# Schematic.net
KiCad netlist of a schematic drawn in EAGLE
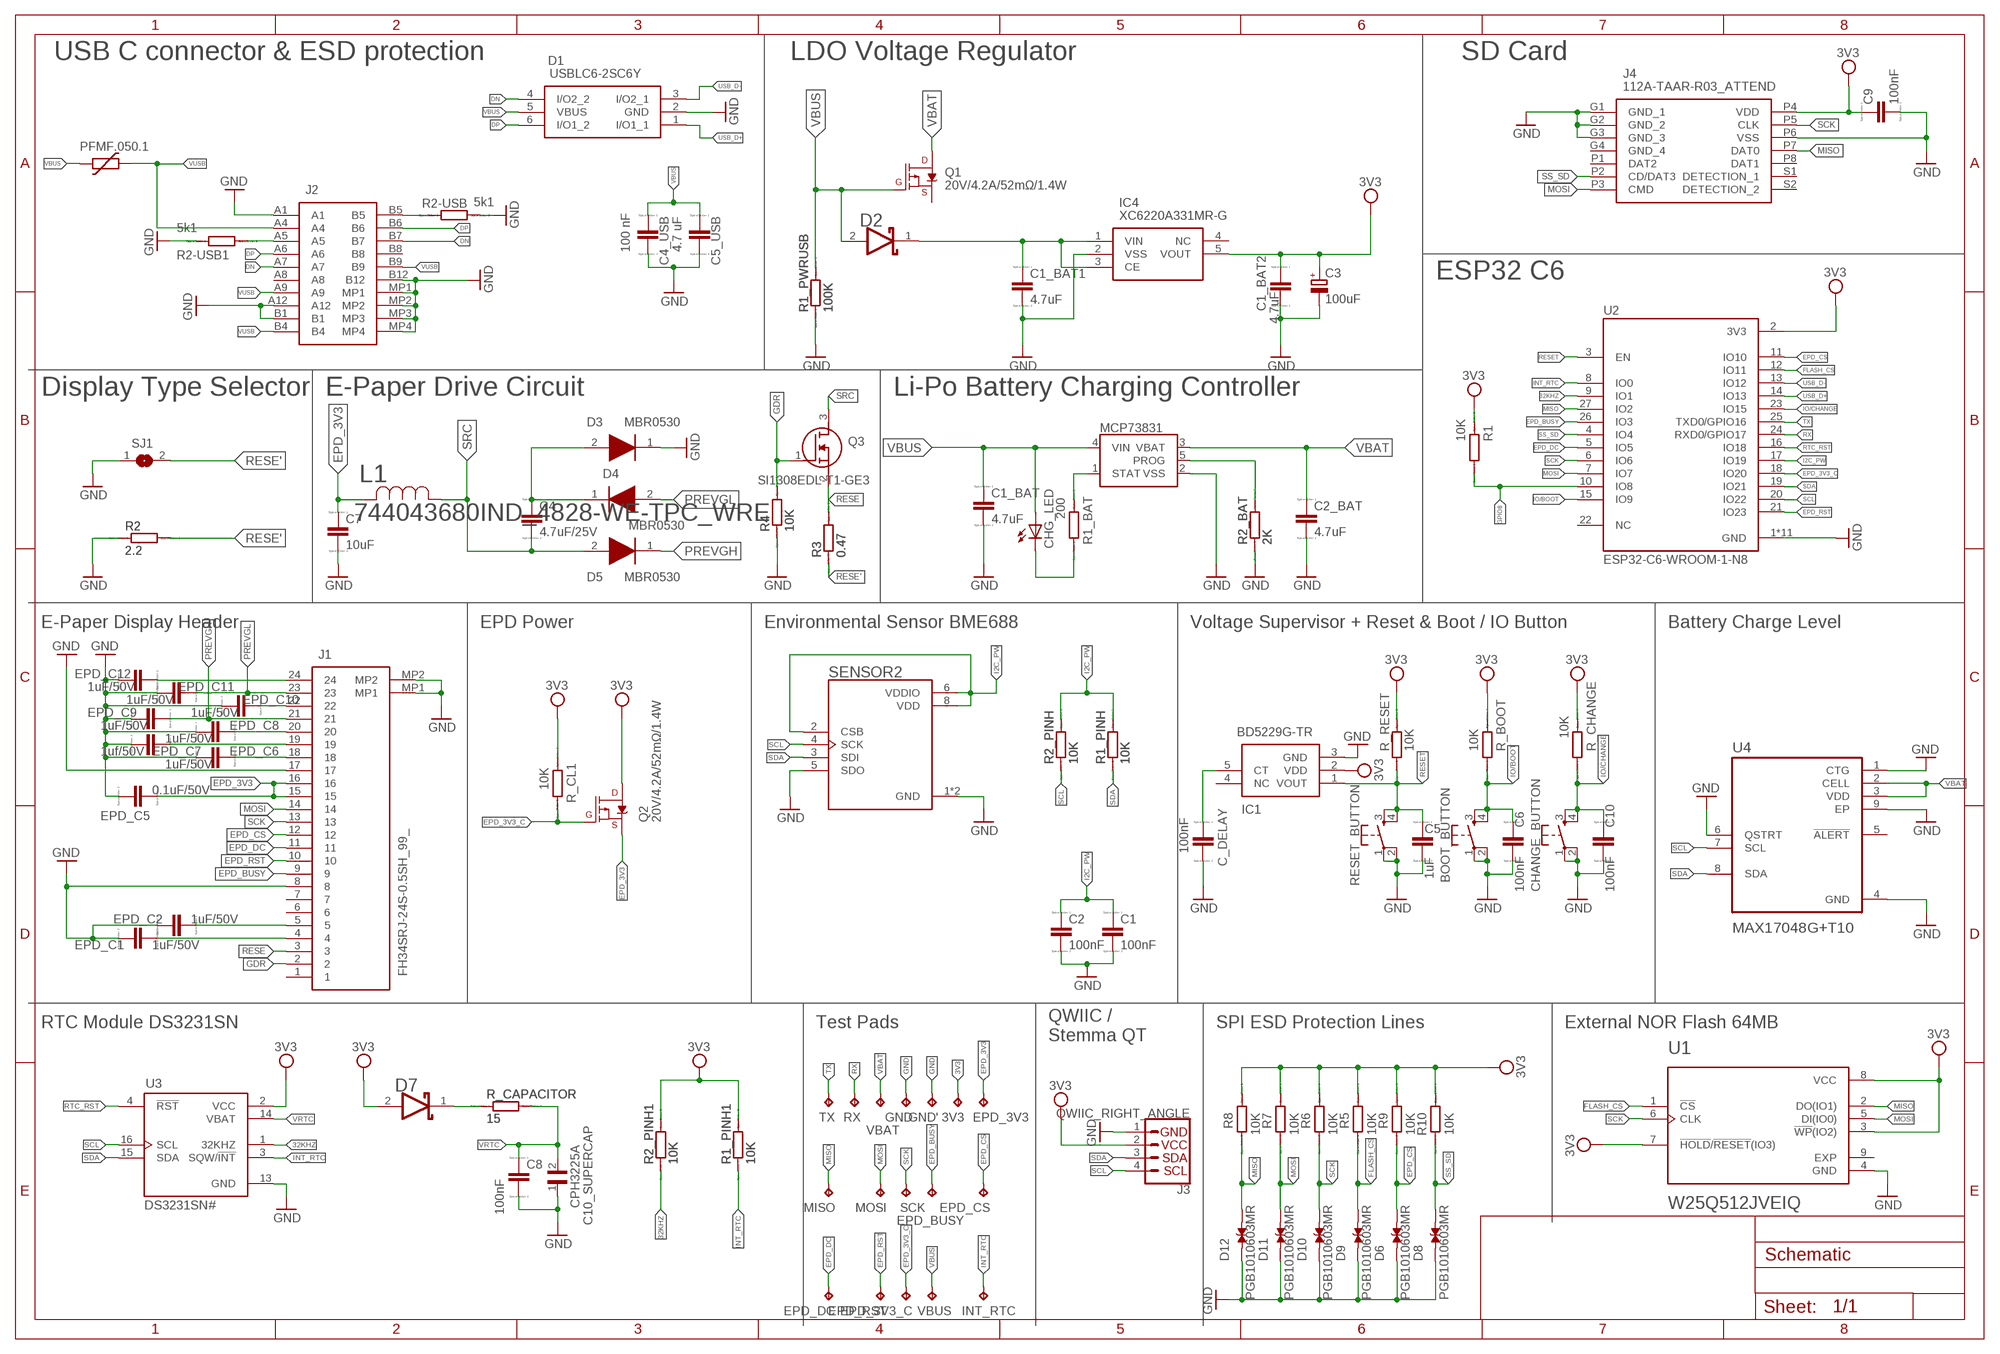
[diagram p0: schematic, sheet 1]

(export (version "E")
  (design (tool "Eeschema 10.0.6"))
  (components
    (comp (ref "3V3")
      (value "TPTP20R")
      (footprint "eagle-import:TP20R")
      (libsource (lib "eagle-import") (part "TPTP20R"))
    )
    (comp (ref "BOOT_BUTTON")
      (value "BUTTON_CUSYOMV1PACKAGE")
      (footprint "eagle-import:MYBUTTON")
      (libsource (lib "eagle-import") (part "BUTTON_CUSYOMV1PACKAGE"))
    )
    (comp (ref "C1")
      (value "100nF")
      (footprint "eagle-import:EAGLE-LTSPICE_C0402")
      (libsource (lib "eagle-import") (part "EAGLE-LTSPICE_CC0402"))
    )
    (comp (ref "C1_BAT")
      (value "4.7uF")
      (footprint "eagle-import:EAGLE-LTSPICE_C0402")
      (libsource (lib "eagle-import") (part "EAGLE-LTSPICE_CC0402"))
    )
    (comp (ref "C1_BAT1")
      (value "4.7uF")
      (footprint "eagle-import:EAGLE-LTSPICE_C0402")
      (libsource (lib "eagle-import") (part "EAGLE-LTSPICE_CC0402"))
    )
    (comp (ref "C1_BAT2")
      (value "4.7uF")
      (footprint "eagle-import:EAGLE-LTSPICE_C0402")
      (libsource (lib "eagle-import") (part "EAGLE-LTSPICE_CC0402"))
    )
    (comp (ref "C2")
      (value "100nF")
      (footprint "eagle-import:EAGLE-LTSPICE_C0402")
      (libsource (lib "eagle-import") (part "EAGLE-LTSPICE_CC0402"))
    )
    (comp (ref "C2_BAT")
      (value "4.7uF")
      (footprint "eagle-import:EAGLE-LTSPICE_C0402")
      (libsource (lib "eagle-import") (part "EAGLE-LTSPICE_CC0402"))
    )
    (comp (ref "C3")
      (value "100uF")
      (footprint "eagle-import:RCL_CT3528")
      (libsource (lib "eagle-import") (part "RCL_CPOL-EUCT3528"))
    )
    (comp (ref "C4")
      (value "4.7uF/25V")
      (footprint "eagle-import:EAGLE-LTSPICE_C0402")
      (libsource (lib "eagle-import") (part "EAGLE-LTSPICE_CC0402"))
    )
    (comp (ref "C4_USB")
      (value "100 nF")
      (footprint "eagle-import:EAGLE-LTSPICE_C0402")
      (libsource (lib "eagle-import") (part "EAGLE-LTSPICE_CC0402"))
    )
    (comp (ref "C5")
      (value "1uF")
      (footprint "eagle-import:EAGLE-LTSPICE_C0402")
      (libsource (lib "eagle-import") (part "EAGLE-LTSPICE_CC0402"))
    )
    (comp (ref "C5_USB")
      (value "4.7 uF")
      (footprint "eagle-import:EAGLE-LTSPICE_C0402")
      (libsource (lib "eagle-import") (part "EAGLE-LTSPICE_CC0402"))
    )
    (comp (ref "C6")
      (value "100nF")
      (footprint "eagle-import:EAGLE-LTSPICE_C0402")
      (libsource (lib "eagle-import") (part "EAGLE-LTSPICE_CC0402"))
    )
    (comp (ref "C7")
      (value "10uF")
      (footprint "eagle-import:EAGLE-LTSPICE_C0402")
      (libsource (lib "eagle-import") (part "EAGLE-LTSPICE_CC0402"))
    )
    (comp (ref "C8")
      (value "100nF")
      (footprint "eagle-import:EAGLE-LTSPICE_C0402")
      (libsource (lib "eagle-import") (part "EAGLE-LTSPICE_CC0402"))
    )
    (comp (ref "C9")
      (value "100nF")
      (footprint "eagle-import:EAGLE-LTSPICE_C0402")
      (libsource (lib "eagle-import") (part "EAGLE-LTSPICE_CC0402"))
    )
    (comp (ref "C10")
      (value "100nF")
      (footprint "eagle-import:EAGLE-LTSPICE_C0402")
      (libsource (lib "eagle-import") (part "EAGLE-LTSPICE_CC0402"))
    )
    (comp (ref "C10_SUPERCAP")
      (value "CPH3225A")
      (footprint "eagle-import:CAPCP3225X100N")
      (fields (field (name "MF") "Seiko Instruments"))
      (libsource (lib "eagle-import") (part "CPH3225A"))
    )
    (comp (ref "CHANGE_BUTTON")
      (value "BUTTON_CUSYOMV1PACKAGE")
      (footprint "eagle-import:MYBUTTON")
      (libsource (lib "eagle-import") (part "BUTTON_CUSYOMV1PACKAGE"))
    )
    (comp (ref "CHG_LED")
      (value "ADAFRUIT_LEDCHIP-LED0603")
      (footprint "eagle-import:ADAFRUIT_CHIP-LED0603")
      (libsource (lib "eagle-import") (part "ADAFRUIT_LEDCHIP-LED0603"))
    )
    (comp (ref "C_DELAY")
      (value "100nF")
      (footprint "eagle-import:EAGLE-LTSPICE_C0402")
      (libsource (lib "eagle-import") (part "EAGLE-LTSPICE_CC0402"))
    )
    (comp (ref "D1")
      (value "USBLC6-2SC6Y")
      (footprint "eagle-import:SOT95P280X145-6N")
      (fields (field (name "MF") "STMicroelectronics"))
      (libsource (lib "eagle-import") (part "USBLC6-2SC6Y"))
    )
    (comp (ref "D2")
      (value "ESP32_WROVER_AVX---SD0805S020S1R0_AVX_SD0805S020S1R0_0_0AVX_SD0805S020S1R0_0_0")
      (footprint "eagle-import:ESP32_WROVER_AVX---SD0805S020S1R0_AVX_SD0805S020S1R0_0")
      (fields
        (field (name "DIGIKEY_PART_NUMBER") "478-7800-1-ND")
        (field (name "MF") "AVX")
        (field (name "MOUSER_PART_NUMBER") "581-SD0805S020S1R0")
      )
      (libsource (lib "eagle-import") (part "ESP32_WROVER_AVX---SD0805S020S1R0_AVX_SD0805S020S1R0_0_0AVX_SD0805S020S1R0_0_0"))
    )
    (comp (ref "D3")
      (value "MBR0530")
      (footprint "eagle-import:SOD3716X135N")
      (fields (field (name "MF") "ON Semiconductor"))
      (libsource (lib "eagle-import") (part "MBR0530"))
    )
    (comp (ref "D4")
      (value "MBR0530")
      (footprint "eagle-import:SOD3716X135N")
      (fields (field (name "MF") "ON Semiconductor"))
      (libsource (lib "eagle-import") (part "MBR0530"))
    )
    (comp (ref "D5")
      (value "MBR0530")
      (footprint "eagle-import:SOD3716X135N")
      (fields (field (name "MF") "ON Semiconductor"))
      (libsource (lib "eagle-import") (part "MBR0530"))
    )
    (comp (ref "D6")
      (value "PGB1010603MR")
      (footprint "eagle-import:DIOC1608X36N")
      (fields (field (name "MF") "Littelfuse Inc."))
      (libsource (lib "eagle-import") (part "PGB1010603MR"))
    )
    (comp (ref "D7")
      (value "ESP32_WROVER_AVX---SD0805S020S1R0_AVX_SD0805S020S1R0_0_0AVX_SD0805S020S1R0_0_0")
      (footprint "eagle-import:ESP32_WROVER_AVX---SD0805S020S1R0_AVX_SD0805S020S1R0_0")
      (fields
        (field (name "DIGIKEY_PART_NUMBER") "478-7800-1-ND")
        (field (name "MF") "AVX")
        (field (name "MOUSER_PART_NUMBER") "581-SD0805S020S1R0")
      )
      (libsource (lib "eagle-import") (part "ESP32_WROVER_AVX---SD0805S020S1R0_AVX_SD0805S020S1R0_0_0AVX_SD0805S020S1R0_0_0"))
    )
    (comp (ref "D8")
      (value "PGB1010603MR")
      (footprint "eagle-import:DIOC1608X36N")
      (fields (field (name "MF") "Littelfuse Inc."))
      (libsource (lib "eagle-import") (part "PGB1010603MR"))
    )
    (comp (ref "D9")
      (value "PGB1010603MR")
      (footprint "eagle-import:DIOC1608X36N")
      (fields (field (name "MF") "Littelfuse Inc."))
      (libsource (lib "eagle-import") (part "PGB1010603MR"))
    )
    (comp (ref "D10")
      (value "PGB1010603MR")
      (footprint "eagle-import:DIOC1608X36N")
      (fields (field (name "MF") "Littelfuse Inc."))
      (libsource (lib "eagle-import") (part "PGB1010603MR"))
    )
    (comp (ref "D11")
      (value "PGB1010603MR")
      (footprint "eagle-import:DIOC1608X36N")
      (fields (field (name "MF") "Littelfuse Inc."))
      (libsource (lib "eagle-import") (part "PGB1010603MR"))
    )
    (comp (ref "D12")
      (value "PGB1010603MR")
      (footprint "eagle-import:DIOC1608X36N")
      (fields (field (name "MF") "Littelfuse Inc."))
      (libsource (lib "eagle-import") (part "PGB1010603MR"))
    )
    (comp (ref "EPD_3V3")
      (value "TPTP20R")
      (footprint "eagle-import:TP20R")
      (libsource (lib "eagle-import") (part "TPTP20R"))
    )
    (comp (ref "EPD_3V3_C")
      (value "TPTP20R")
      (footprint "eagle-import:TP20R")
      (libsource (lib "eagle-import") (part "TPTP20R"))
    )
    (comp (ref "EPD_BUSY")
      (value "TPTP20R")
      (footprint "eagle-import:TP20R")
      (libsource (lib "eagle-import") (part "TPTP20R"))
    )
    (comp (ref "EPD_C1")
      (value "1uF/50V")
      (footprint "eagle-import:EAGLE-LTSPICE_C0402")
      (libsource (lib "eagle-import") (part "EAGLE-LTSPICE_CC0402"))
    )
    (comp (ref "EPD_C2")
      (value "1uF/50V")
      (footprint "eagle-import:EAGLE-LTSPICE_C0402")
      (libsource (lib "eagle-import") (part "EAGLE-LTSPICE_CC0402"))
    )
    (comp (ref "EPD_C5")
      (value "0.1uF/50V")
      (footprint "eagle-import:EAGLE-LTSPICE_C0402")
      (libsource (lib "eagle-import") (part "EAGLE-LTSPICE_CC0402"))
    )
    (comp (ref "EPD_C6")
      (value "1uF/50V")
      (footprint "eagle-import:EAGLE-LTSPICE_C0402")
      (libsource (lib "eagle-import") (part "EAGLE-LTSPICE_CC0402"))
    )
    (comp (ref "EPD_C7")
      (value "1uf/50V")
      (footprint "eagle-import:EAGLE-LTSPICE_C0402")
      (libsource (lib "eagle-import") (part "EAGLE-LTSPICE_CC0402"))
    )
    (comp (ref "EPD_C8")
      (value "1uF/50V")
      (footprint "eagle-import:EAGLE-LTSPICE_C0402")
      (libsource (lib "eagle-import") (part "EAGLE-LTSPICE_CC0402"))
    )
    (comp (ref "EPD_C9")
      (value "1uF/50V")
      (footprint "eagle-import:EAGLE-LTSPICE_C0402")
      (libsource (lib "eagle-import") (part "EAGLE-LTSPICE_CC0402"))
    )
    (comp (ref "EPD_C10")
      (value "1uF/50V")
      (footprint "eagle-import:EAGLE-LTSPICE_C0402")
      (libsource (lib "eagle-import") (part "EAGLE-LTSPICE_CC0402"))
    )
    (comp (ref "EPD_C11")
      (value "1uF/50V")
      (footprint "eagle-import:EAGLE-LTSPICE_C0402")
      (libsource (lib "eagle-import") (part "EAGLE-LTSPICE_CC0402"))
    )
    (comp (ref "EPD_C12")
      (value "1uF/50V")
      (footprint "eagle-import:EAGLE-LTSPICE_C0402")
      (libsource (lib "eagle-import") (part "EAGLE-LTSPICE_CC0402"))
    )
    (comp (ref "EPD_CS")
      (value "TPTP20R")
      (footprint "eagle-import:TP20R")
      (libsource (lib "eagle-import") (part "TPTP20R"))
    )
    (comp (ref "EPD_DC")
      (value "TPTP20R")
      (footprint "eagle-import:TP20R")
      (libsource (lib "eagle-import") (part "TPTP20R"))
    )
    (comp (ref "EPD_RST")
      (value "TPTP20R")
      (footprint "eagle-import:TP20R")
      (libsource (lib "eagle-import") (part "TPTP20R"))
    )
    (comp (ref "GND")
      (value "TPTP20R")
      (footprint "eagle-import:TP20R")
      (libsource (lib "eagle-import") (part "TPTP20R"))
    )
    (comp (ref "GND'")
      (value "TPTP20R")
      (footprint "eagle-import:TP20R")
      (libsource (lib "eagle-import") (part "TPTP20R"))
    )
    (comp (ref "IC1")
      (value "BD5229G-TR")
      (footprint "eagle-import:SOT95P280X125-5N")
      (fields (field (name "MOUSER_PART_NUMBER") "755-BD5229G-TR"))
      (libsource (lib "eagle-import") (part "BD5229G-TR"))
    )
    (comp (ref "IC4")
      (value "XC6220A331MR-G")
      (footprint "eagle-import:SOT95P280X120-5N")
      (fields (field (name "MOUSER_PART_NUMBER") "865-XC6220A331MR-G"))
      (libsource (lib "eagle-import") (part "XC6220A331MR-G"))
    )
    (comp (ref "INT_RTC")
      (value "TPTP20R")
      (footprint "eagle-import:TP20R")
      (libsource (lib "eagle-import") (part "TPTP20R"))
    )
    (comp (ref "J1")
      (value "FH34SRJ-24S-0.5SH_99_")
      (footprint "eagle-import:FH34SRJ24S05SH99")
      (fields
        (field (name "MANUFACTURER_PART_NUMBER") "FH34SRJ-24S-0.5SH(99)")
        (field (name "MOUSER_PART_NUMBER") "798-FH34SRJ24S05SH99")
      )
      (libsource (lib "eagle-import") (part "FH34SRJ-24S-0.5SH_99_"))
    )
    (comp (ref "J2")
      (value "SAMACSYS_PARTS_USB4110-GF-A")
      (footprint "eagle-import:SAMACSYS_PARTS_USB4110GFA")
      (fields
        (field (name "MANUFACTURER_PART_NUMBER") "USB4110-GF-A")
        (field (name "MOUSER_PART_NUMBER") "640-USB4110-GF-A")
      )
      (libsource (lib "eagle-import") (part "SAMACSYS_PARTS_USB4110-GF-A"))
    )
    (comp (ref "J3")
      (value "QWIIC_RIGHT_ANGLE")
      (footprint "eagle-import:JST04_1MM_RA")
      (libsource (lib "eagle-import") (part "QWIIC_CONNECTORJS-1MM"))
    )
    (comp (ref "J4")
      (value "112A-TAAR-R03_ATTEND")
      (footprint "eagle-import:112ATAARR03ATTEND")
      (fields (field (name "MANUFACTURER_PART_NUMBER") "112A-TAAR-R03 ATTEND"))
      (libsource (lib "eagle-import") (part "112A-TAAR-R03_ATTEND"))
    )
    (comp (ref "L1")
      (value "744043680IND_4828-WE-TPC_WRE")
      (footprint "eagle-import:IND_4828-WE-TPC_WRE")
      (fields
        (field (name "MANUFACTURER_PART_NUMBER") "744043680")
        (field (name "COPYRIGHT") "Copyright (C) 2024 Ultra Librarian. All rights reserved.")
      )
      (libsource (lib "eagle-import") (part "744043680IND_4828-WE-TPC_WRE"))
    )
    (comp (ref "MCP73831")
      (value "ESP32_WROVER_SPARKFUN-IC-POWER_MCP73831")
      (footprint "eagle-import:ESP32_WROVER_SPARKFUN-IC-POWER_SOT23-5")
      (libsource (lib "eagle-import") (part "ESP32_WROVER_SPARKFUN-IC-POWER_MCP73831"))
    )
    (comp (ref "MISO")
      (value "TPTP20R")
      (footprint "eagle-import:TP20R")
      (libsource (lib "eagle-import") (part "TPTP20R"))
    )
    (comp (ref "MOSI")
      (value "TPTP20R")
      (footprint "eagle-import:TP20R")
      (libsource (lib "eagle-import") (part "TPTP20R"))
    )
    (comp (ref "PFMF.050.1")
      (value "VARISTOR_3216")
      (footprint "eagle-import:VARC3216X102N")
      (libsource (lib "eagle-import") (part "VARISTOR3216_"))
    )
    (comp (ref "Q1")
      (value "20V/4.2A/52mΩ/1.4W")
      (footprint "eagle-import:ESP32_WROVER_SPARKFUN-DISCRETESEMI_SOT23-3")
      (libsource (lib "eagle-import") (part "ESP32_WROVER_SPARKFUN-DISCRETESEMI_MOSFET_PCH-DMG2305UX-7"))
    )
    (comp (ref "Q2")
      (value "20V/4.2A/52mΩ/1.4W")
      (footprint "eagle-import:ESP32_WROVER_SPARKFUN-DISCRETESEMI_SOT23-3")
      (libsource (lib "eagle-import") (part "ESP32_WROVER_SPARKFUN-DISCRETESEMI_MOSFET_PCH-DMG2305UX-7"))
    )
    (comp (ref "Q3")
      (value "SI1308EDL-T1-GE3")
      (footprint "eagle-import:SOT65P210X110-3N")
      (fields (field (name "MF") "Vishay Siliconix"))
      (libsource (lib "eagle-import") (part "SI1308EDL-T1-GE3"))
    )
    (comp (ref "R1")
      (value "10K")
      (footprint "eagle-import:ESP32_WROVER_EAGLE-LTSPICE_R0402")
      (libsource (lib "eagle-import") (part "ESP32_WROVER_EAGLE-LTSPICE_RR0402"))
    )
    (comp (ref "R1_BAT")
      (value "200")
      (footprint "eagle-import:ESP32_WROVER_EAGLE-LTSPICE_R0402")
      (libsource (lib "eagle-import") (part "ESP32_WROVER_EAGLE-LTSPICE_RR0402"))
    )
    (comp (ref "R1_PINH")
      (value "10K")
      (footprint "eagle-import:ESP32_WROVER_EAGLE-LTSPICE_R0402")
      (libsource (lib "eagle-import") (part "ESP32_WROVER_EAGLE-LTSPICE_RR0402"))
    )
    (comp (ref "R1_PINH1")
      (value "10K")
      (footprint "eagle-import:ESP32_WROVER_EAGLE-LTSPICE_R0402")
      (libsource (lib "eagle-import") (part "ESP32_WROVER_EAGLE-LTSPICE_RR0402"))
    )
    (comp (ref "R1_PWRUSB")
      (value "100K")
      (footprint "eagle-import:ESP32_WROVER_EAGLE-LTSPICE_R0402")
      (libsource (lib "eagle-import") (part "ESP32_WROVER_EAGLE-LTSPICE_RR0402"))
    )
    (comp (ref "R2")
      (value "2.2")
      (footprint "eagle-import:ESP32_WROVER_EAGLE-LTSPICE_R0402")
      (libsource (lib "eagle-import") (part "ESP32_WROVER_EAGLE-LTSPICE_RR0402"))
    )
    (comp (ref "R2-USB")
      (value "5k1")
      (footprint "eagle-import:ESP32_WROVER_EAGLE-LTSPICE_R0402")
      (libsource (lib "eagle-import") (part "ESP32_WROVER_EAGLE-LTSPICE_RR0402"))
    )
    (comp (ref "R2-USB1")
      (value "5k1")
      (footprint "eagle-import:ESP32_WROVER_EAGLE-LTSPICE_R0402")
      (libsource (lib "eagle-import") (part "ESP32_WROVER_EAGLE-LTSPICE_RR0402"))
    )
    (comp (ref "R2_BAT")
      (value "2K")
      (footprint "eagle-import:ESP32_WROVER_EAGLE-LTSPICE_R0402")
      (libsource (lib "eagle-import") (part "ESP32_WROVER_EAGLE-LTSPICE_RR0402"))
    )
    (comp (ref "R2_PINH")
      (value "10K")
      (footprint "eagle-import:ESP32_WROVER_EAGLE-LTSPICE_R0402")
      (libsource (lib "eagle-import") (part "ESP32_WROVER_EAGLE-LTSPICE_RR0402"))
    )
    (comp (ref "R2_PINH1")
      (value "10K")
      (footprint "eagle-import:ESP32_WROVER_EAGLE-LTSPICE_R0402")
      (libsource (lib "eagle-import") (part "ESP32_WROVER_EAGLE-LTSPICE_RR0402"))
    )
    (comp (ref "R3")
      (value "0.47")
      (footprint "eagle-import:ESP32_WROVER_EAGLE-LTSPICE_R0402")
      (libsource (lib "eagle-import") (part "ESP32_WROVER_EAGLE-LTSPICE_RR0402"))
    )
    (comp (ref "R4")
      (value "10K")
      (footprint "eagle-import:ESP32_WROVER_EAGLE-LTSPICE_R0402")
      (libsource (lib "eagle-import") (part "ESP32_WROVER_EAGLE-LTSPICE_RR0402"))
    )
    (comp (ref "R5")
      (value "10K")
      (footprint "eagle-import:ESP32_WROVER_EAGLE-LTSPICE_R0402")
      (libsource (lib "eagle-import") (part "ESP32_WROVER_EAGLE-LTSPICE_RR0402"))
    )
    (comp (ref "R6")
      (value "10K")
      (footprint "eagle-import:ESP32_WROVER_EAGLE-LTSPICE_R0402")
      (libsource (lib "eagle-import") (part "ESP32_WROVER_EAGLE-LTSPICE_RR0402"))
    )
    (comp (ref "R7")
      (value "10K")
      (footprint "eagle-import:ESP32_WROVER_EAGLE-LTSPICE_R0402")
      (libsource (lib "eagle-import") (part "ESP32_WROVER_EAGLE-LTSPICE_RR0402"))
    )
    (comp (ref "R8")
      (value "10K")
      (footprint "eagle-import:ESP32_WROVER_EAGLE-LTSPICE_R0402")
      (libsource (lib "eagle-import") (part "ESP32_WROVER_EAGLE-LTSPICE_RR0402"))
    )
    (comp (ref "R9")
      (value "10K")
      (footprint "eagle-import:ESP32_WROVER_EAGLE-LTSPICE_R0402")
      (libsource (lib "eagle-import") (part "ESP32_WROVER_EAGLE-LTSPICE_RR0402"))
    )
    (comp (ref "R10")
      (value "10K")
      (footprint "eagle-import:ESP32_WROVER_EAGLE-LTSPICE_R0402")
      (libsource (lib "eagle-import") (part "ESP32_WROVER_EAGLE-LTSPICE_RR0402"))
    )
    (comp (ref "RESET_BUTTON")
      (value "BUTTON_CUSYOMV1PACKAGE")
      (footprint "eagle-import:MYBUTTON")
      (libsource (lib "eagle-import") (part "BUTTON_CUSYOMV1PACKAGE"))
    )
    (comp (ref "RX")
      (value "TPTP20R")
      (footprint "eagle-import:TP20R")
      (libsource (lib "eagle-import") (part "TPTP20R"))
    )
    (comp (ref "R_BOOT")
      (value "10K")
      (footprint "eagle-import:ESP32_WROVER_EAGLE-LTSPICE_R0402")
      (libsource (lib "eagle-import") (part "ESP32_WROVER_EAGLE-LTSPICE_RR0402"))
    )
    (comp (ref "R_CAPACITOR")
      (value "15")
      (footprint "eagle-import:ESP32_WROVER_EAGLE-LTSPICE_R0402")
      (libsource (lib "eagle-import") (part "ESP32_WROVER_EAGLE-LTSPICE_RR0402"))
    )
    (comp (ref "R_CHANGE")
      (value "10K")
      (footprint "eagle-import:ESP32_WROVER_EAGLE-LTSPICE_R0402")
      (libsource (lib "eagle-import") (part "ESP32_WROVER_EAGLE-LTSPICE_RR0402"))
    )
    (comp (ref "R_CL1")
      (value "10K")
      (footprint "eagle-import:ESP32_WROVER_EAGLE-LTSPICE_R0402")
      (libsource (lib "eagle-import") (part "ESP32_WROVER_EAGLE-LTSPICE_RR0402"))
    )
    (comp (ref "R_RESET")
      (value "10K")
      (footprint "eagle-import:ESP32_WROVER_EAGLE-LTSPICE_R0402")
      (libsource (lib "eagle-import") (part "ESP32_WROVER_EAGLE-LTSPICE_RR0402"))
    )
    (comp (ref "SCK")
      (value "TPTP20R")
      (footprint "eagle-import:TP20R")
      (libsource (lib "eagle-import") (part "TPTP20R"))
    )
    (comp (ref "SENSOR2")
      (value "ESP32_WROVER_BME680_BME680")
      (footprint "eagle-import:ESP32_WROVER_BME680_PSON80P300X300X100-8N")
      (fields (field (name "MF") "Bosch Sensortec") (field (name "MP") "BME680"))
      (libsource (lib "eagle-import") (part "ESP32_WROVER_BME680_BME680"))
    )
    (comp (ref "SJ1") (value "SJ") (footprint "eagle-import:SJ") (libsource (lib "eagle-import") (part "SJ")))
    (comp (ref "TX")
      (value "TPTP20R")
      (footprint "eagle-import:TP20R")
      (libsource (lib "eagle-import") (part "TPTP20R"))
    )
    (comp (ref "U1")
      (value "W25Q512JVEIQ")
      (footprint "eagle-import:SON127P600X800X80-9N")
      (fields (field (name "MF") "Winbond Electronics"))
      (libsource (lib "eagle-import") (part "W25Q512JVEIQ"))
    )
    (comp (ref "U2")
      (value "ESP32-C6-WROOM-1-N8")
      (footprint "eagle-import:XCVR_ESP32-C6-WROOM-1-N8")
      (fields (field (name "MF") "Espressif Systems"))
      (libsource (lib "eagle-import") (part "ESP32-C6-WROOM-1-N8"))
    )
    (comp (ref "U3")
      (value "DS3231SN#")
      (footprint "eagle-import:SOIC127P1032X265-16N")
      (fields (field (name "MF") "Analog Devices"))
      (libsource (lib "eagle-import") (part "DS3231SN#"))
    )
    (comp (ref "U4")
      (value "MAX17048G+T10")
      (footprint "eagle-import:SON50P200X200X80-9N")
      (fields (field (name "MF") "Analog Devices"))
      (libsource (lib "eagle-import") (part "MAX17048G+T10"))
    )
    (comp (ref "VBAT")
      (value "TPTP20R")
      (footprint "eagle-import:TP20R")
      (libsource (lib "eagle-import") (part "TPTP20R"))
    )
    (comp (ref "VBUS")
      (value "TPTP20R")
      (footprint "eagle-import:TP20R")
      (libsource (lib "eagle-import") (part "TPTP20R"))
    )
  )
  (nets
    (net (code "1") (name "3V3") (class "Default")
      (node (ref "3V3") (pin "TP") (pinfunction "TP_TP") (pintype "input"))
      (node (ref "C1_BAT2") (pin "1") (pinfunction "1_1") (pintype "passive"))
      (node (ref "C3") (pin "+") (pinfunction "+_+") (pintype "passive"))
      (node (ref "C9") (pin "1") (pinfunction "1_1") (pintype "passive"))
      (node (ref "D7") (pin "2") (pinfunction "ANODE_2") (pintype "bidirectional"))
      (node (ref "IC1") (pin "2") (pinfunction "VDD_2") (pintype "bidirectional"))
      (node (ref "IC4") (pin "5") (pinfunction "VOUT_5") (pintype "bidirectional"))
      (node (ref "J3") (pin "2") (pinfunction "2_2") (pintype "power_in"))
      (node (ref "J4") (pin "P4") (pinfunction "VDD_P4") (pintype "bidirectional"))
      (node (ref "Q2") (pin "3") (pinfunction "D_3") (pintype "bidirectional"))
      (node (ref "R1") (pin "2") (pinfunction "2_2") (pintype "passive"))
      (node (ref "R10") (pin "1") (pinfunction "1_1") (pintype "passive"))
      (node (ref "R1_PINH1") (pin "2") (pinfunction "2_2") (pintype "passive"))
      (node (ref "R2_PINH1") (pin "2") (pinfunction "2_2") (pintype "passive"))
      (node (ref "R5") (pin "1") (pinfunction "1_1") (pintype "passive"))
      (node (ref "R6") (pin "1") (pinfunction "1_1") (pintype "passive"))
      (node (ref "R7") (pin "1") (pinfunction "1_1") (pintype "passive"))
      (node (ref "R8") (pin "1") (pinfunction "1_1") (pintype "passive"))
      (node (ref "R9") (pin "1") (pinfunction "1_1") (pintype "passive"))
      (node (ref "R_BOOT") (pin "2") (pinfunction "2_2") (pintype "passive"))
      (node (ref "R_CHANGE") (pin "2") (pinfunction "2_2") (pintype "passive"))
      (node (ref "R_CL1") (pin "2") (pinfunction "2_2") (pintype "passive"))
      (node (ref "R_RESET") (pin "2") (pinfunction "2_2") (pintype "passive"))
      (node (ref "U1") (pin "3") (pinfunction "~{WP}(IO2)_3") (pintype "bidirectional"))
      (node (ref "U1") (pin "7") (pinfunction "~{HOLD}/~{RESET}(IO3)_7") (pintype "bidirectional"))
      (node (ref "U1") (pin "8") (pinfunction "VCC_8") (pintype "power_in"))
      (node (ref "U2") (pin "2") (pinfunction "3V3_2") (pintype "power_in"))
      (node (ref "U3") (pin "2") (pinfunction "VCC_2") (pintype "power_in"))
    )
    (net (code "2") (name "32KHZ") (class "Default")
      (node (ref "R2_PINH1") (pin "1") (pinfunction "1_1") (pintype "passive"))
      (node (ref "U2") (pin "9") (pinfunction "IO1_9") (pintype "bidirectional"))
      (node (ref "U3") (pin "1") (pinfunction "32KHZ_1") (pintype "output"))
    )
    (net (code "3") (name "DN") (class "Default")
      (node (ref "D1") (pin "4") (pinfunction "I/O2_2_4") (pintype "bidirectional"))
      (node (ref "J2") (pin "A7") (pinfunction "A7_A7") (pintype "bidirectional"))
      (node (ref "J2") (pin "B7") (pinfunction "B7_B7") (pintype "bidirectional"))
    )
    (net (code "4") (name "DP") (class "Default")
      (node (ref "D1") (pin "6") (pinfunction "I/O1_2_6") (pintype "bidirectional"))
      (node (ref "J2") (pin "A6") (pinfunction "A6_A6") (pintype "bidirectional"))
      (node (ref "J2") (pin "B6") (pinfunction "B6_B6") (pintype "bidirectional"))
    )
    (net (code "5") (name "EPD_3V3") (class "Default")
      (node (ref "C7") (pin "1") (pinfunction "1_1") (pintype "passive"))
      (node (ref "EPD_3V3") (pin "TP") (pinfunction "TP_TP") (pintype "input"))
      (node (ref "EPD_C5") (pin "1") (pinfunction "1_1") (pintype "passive"))
      (node (ref "J1") (pin "15") (pinfunction "15_15") (pintype "bidirectional"))
      (node (ref "J1") (pin "16") (pinfunction "16_16") (pintype "bidirectional"))
      (node (ref "L1") (pin "2") (pinfunction "2_2") (pintype "passive"))
      (node (ref "Q2") (pin "2") (pinfunction "S_2") (pintype "bidirectional"))
    )
    (net (code "6") (name "EPD_3V3_C") (class "Default")
      (node (ref "EPD_3V3_C") (pin "TP") (pinfunction "TP_TP") (pintype "input"))
      (node (ref "Q2") (pin "1") (pinfunction "G_1") (pintype "bidirectional"))
      (node (ref "R_CL1") (pin "1") (pinfunction "1_1") (pintype "passive"))
      (node (ref "U2") (pin "18") (pinfunction "IO20_18") (pintype "bidirectional"))
    )
    (net (code "7") (name "EPD_BUSY") (class "Default")
      (node (ref "EPD_BUSY") (pin "TP") (pinfunction "TP_TP") (pintype "input"))
      (node (ref "J1") (pin "9") (pinfunction "9_9") (pintype "bidirectional"))
      (node (ref "U2") (pin "26") (pinfunction "IO3_26") (pintype "bidirectional"))
    )
    (net (code "8") (name "EPD_CS") (class "Default")
      (node (ref "D6") (pin "2") (pinfunction "2_2") (pintype "passive"))
      (node (ref "EPD_CS") (pin "TP") (pinfunction "TP_TP") (pintype "input"))
      (node (ref "J1") (pin "12") (pinfunction "12_12") (pintype "bidirectional"))
      (node (ref "R9") (pin "2") (pinfunction "2_2") (pintype "passive"))
      (node (ref "U2") (pin "11") (pinfunction "IO10_11") (pintype "bidirectional"))
    )
    (net (code "9") (name "EPD_DC") (class "Default")
      (node (ref "EPD_DC") (pin "TP") (pinfunction "TP_TP") (pintype "input"))
      (node (ref "J1") (pin "11") (pinfunction "11_11") (pintype "bidirectional"))
      (node (ref "U2") (pin "5") (pinfunction "IO5_5") (pintype "bidirectional"))
    )
    (net (code "10") (name "EPD_RST") (class "Default")
      (node (ref "EPD_RST") (pin "TP") (pinfunction "TP_TP") (pintype "input"))
      (node (ref "J1") (pin "10") (pinfunction "10_10") (pintype "bidirectional"))
      (node (ref "U2") (pin "21") (pinfunction "IO23_21") (pintype "bidirectional"))
    )
    (net (code "11") (name "FLASH_CS") (class "Default")
      (node (ref "D9") (pin "2") (pinfunction "2_2") (pintype "passive"))
      (node (ref "R5") (pin "2") (pinfunction "2_2") (pintype "passive"))
      (node (ref "U1") (pin "1") (pinfunction "~{CS}_1") (pintype "input"))
      (node (ref "U2") (pin "12") (pinfunction "IO11_12") (pintype "bidirectional"))
    )
    (net (code "12") (name "GDR") (class "Default")
      (node (ref "J1") (pin "2") (pinfunction "2_2") (pintype "bidirectional"))
      (node (ref "Q3") (pin "1") (pinfunction "G_1") (pintype "bidirectional"))
      (node (ref "R4") (pin "2") (pinfunction "2_2") (pintype "passive"))
    )
    (net (code "13") (name "GND") (class "Default")
      (node (ref "BOOT_BUTTON") (pin "1") (pinfunction "1_1") (pintype "passive"))
      (node (ref "BOOT_BUTTON") (pin "2") (pinfunction "2_2") (pintype "passive"))
      (node (ref "C1") (pin "2") (pinfunction "2_2") (pintype "passive"))
      (node (ref "C10") (pin "2") (pinfunction "2_2") (pintype "passive"))
      (node (ref "C10_SUPERCAP") (pin "1") (pinfunction "1_1") (pintype "passive"))
      (node (ref "C1_BAT") (pin "2") (pinfunction "2_2") (pintype "passive"))
      (node (ref "C1_BAT1") (pin "2") (pinfunction "2_2") (pintype "passive"))
      (node (ref "C1_BAT2") (pin "2") (pinfunction "2_2") (pintype "passive"))
      (node (ref "C2") (pin "2") (pinfunction "2_2") (pintype "passive"))
      (node (ref "C2_BAT") (pin "2") (pinfunction "2_2") (pintype "passive"))
      (node (ref "C3") (pin "-") (pinfunction "-_-") (pintype "passive"))
      (node (ref "C4_USB") (pin "2") (pinfunction "2_2") (pintype "passive"))
      (node (ref "C5") (pin "2") (pinfunction "2_2") (pintype "passive"))
      (node (ref "C5_USB") (pin "2") (pinfunction "2_2") (pintype "passive"))
      (node (ref "C6") (pin "2") (pinfunction "2_2") (pintype "passive"))
      (node (ref "C7") (pin "2") (pinfunction "2_2") (pintype "passive"))
      (node (ref "C8") (pin "2") (pinfunction "2_2") (pintype "passive"))
      (node (ref "C9") (pin "2") (pinfunction "2_2") (pintype "passive"))
      (node (ref "CHANGE_BUTTON") (pin "1") (pinfunction "1_1") (pintype "passive"))
      (node (ref "CHANGE_BUTTON") (pin "2") (pinfunction "2_2") (pintype "passive"))
      (node (ref "C_DELAY") (pin "2") (pinfunction "2_2") (pintype "passive"))
      (node (ref "D1") (pin "2") (pinfunction "GND_2") (pintype "bidirectional"))
      (node (ref "D10") (pin "1") (pinfunction "1_1") (pintype "passive"))
      (node (ref "D11") (pin "1") (pinfunction "1_1") (pintype "passive"))
      (node (ref "D12") (pin "1") (pinfunction "1_1") (pintype "passive"))
      (node (ref "D3") (pin "1") (pinfunction "K_1") (pintype "bidirectional"))
      (node (ref "D6") (pin "1") (pinfunction "1_1") (pintype "passive"))
      (node (ref "D8") (pin "1") (pinfunction "1_1") (pintype "passive"))
      (node (ref "D9") (pin "1") (pinfunction "1_1") (pintype "passive"))
      (node (ref "EPD_C1") (pin "2") (pinfunction "2_2") (pintype "passive"))
      (node (ref "EPD_C10") (pin "2") (pinfunction "2_2") (pintype "passive"))
      (node (ref "EPD_C11") (pin "2") (pinfunction "2_2") (pintype "passive"))
      (node (ref "EPD_C12") (pin "2") (pinfunction "2_2") (pintype "passive"))
      (node (ref "EPD_C2") (pin "2") (pinfunction "2_2") (pintype "passive"))
      (node (ref "EPD_C5") (pin "2") (pinfunction "2_2") (pintype "passive"))
      (node (ref "EPD_C6") (pin "2") (pinfunction "2_2") (pintype "passive"))
      (node (ref "EPD_C7") (pin "2") (pinfunction "2_2") (pintype "passive"))
      (node (ref "EPD_C8") (pin "2") (pinfunction "2_2") (pintype "passive"))
      (node (ref "EPD_C9") (pin "2") (pinfunction "2_2") (pintype "passive"))
      (node (ref "GND") (pin "TP") (pinfunction "TP_TP") (pintype "input"))
      (node (ref "GND'") (pin "TP") (pinfunction "TP_TP") (pintype "input"))
      (node (ref "IC1") (pin "3") (pinfunction "GND_3") (pintype "bidirectional"))
      (node (ref "IC4") (pin "2") (pinfunction "VSS_2") (pintype "bidirectional"))
      (node (ref "J1") (pin "17") (pinfunction "17_17") (pintype "bidirectional"))
      (node (ref "J1") (pin "8") (pinfunction "8_8") (pintype "bidirectional"))
      (node (ref "J1") (pin "MP1") (pinfunction "MP1_MP1") (pintype "bidirectional"))
      (node (ref "J1") (pin "MP2") (pinfunction "MP2_MP2") (pintype "bidirectional"))
      (node (ref "J2") (pin "A1") (pinfunction "A1_A1") (pintype "bidirectional"))
      (node (ref "J2") (pin "A12") (pinfunction "A12_A12") (pintype "bidirectional"))
      (node (ref "J2") (pin "B1") (pinfunction "B1_B1") (pintype "bidirectional"))
      (node (ref "J2") (pin "B12") (pinfunction "B12_B12") (pintype "bidirectional"))
      (node (ref "J2") (pin "MP1") (pinfunction "MP1_MP1") (pintype "bidirectional"))
      (node (ref "J2") (pin "MP2") (pinfunction "MP2_MP2") (pintype "bidirectional"))
      (node (ref "J2") (pin "MP3") (pinfunction "MP3_MP3") (pintype "bidirectional"))
      (node (ref "J2") (pin "MP4") (pinfunction "MP4_MP4") (pintype "bidirectional"))
      (node (ref "J3") (pin "1") (pinfunction "1_1") (pintype "power_in"))
      (node (ref "J4") (pin "G1") (pinfunction "GND_1_G1") (pintype "bidirectional"))
      (node (ref "J4") (pin "G2") (pinfunction "GND_2_G2") (pintype "bidirectional"))
      (node (ref "J4") (pin "G3") (pinfunction "GND_3_G3") (pintype "bidirectional"))
      (node (ref "J4") (pin "P6") (pinfunction "VSS_P6") (pintype "bidirectional"))
      (node (ref "MCP73831") (pin "2") (pinfunction "VSS_2") (pintype "power_in"))
      (node (ref "R1_PWRUSB") (pin "1") (pinfunction "1_1") (pintype "passive"))
      (node (ref "R2") (pin "1") (pinfunction "1_1") (pintype "passive"))
      (node (ref "R2-USB") (pin "2") (pinfunction "2_2") (pintype "passive"))
      (node (ref "R2-USB1") (pin "1") (pinfunction "1_1") (pintype "passive"))
      (node (ref "R2_BAT") (pin "1") (pinfunction "1_1") (pintype "passive"))
      (node (ref "R4") (pin "1") (pinfunction "1_1") (pintype "passive"))
      (node (ref "RESET_BUTTON") (pin "1") (pinfunction "1_1") (pintype "passive"))
      (node (ref "RESET_BUTTON") (pin "2") (pinfunction "2_2") (pintype "passive"))
      (node (ref "SENSOR2") (pin "1") (pinfunction "GND_1") (pintype "power_in"))
      (node (ref "SENSOR2") (pin "5") (pinfunction "SDO_5") (pintype "bidirectional"))
      (node (ref "SENSOR2") (pin "7") (pinfunction "GND_7") (pintype "power_in"))
      (node (ref "SJ1") (pin "1") (pinfunction "1_1") (pintype "passive"))
      (node (ref "U1") (pin "4") (pinfunction "GND_4") (pintype "power_in"))
      (node (ref "U2") (pin "1") (pinfunction "GND_1") (pintype "power_in"))
      (node (ref "U2") (pin "28") (pinfunction "GND_28") (pintype "power_in"))
      (node (ref "U2") (pin "29_1") (pinfunction "GND_29_1") (pintype "power_in"))
      (node (ref "U2") (pin "29_2") (pinfunction "GND_29_2") (pintype "power_in"))
      (node (ref "U2") (pin "29_3") (pinfunction "GND_29_3") (pintype "power_in"))
      (node (ref "U2") (pin "29_4") (pinfunction "GND_29_4") (pintype "power_in"))
      (node (ref "U2") (pin "29_5") (pinfunction "GND_29_5") (pintype "power_in"))
      (node (ref "U2") (pin "29_6") (pinfunction "GND_29_6") (pintype "power_in"))
      (node (ref "U2") (pin "29_7") (pinfunction "GND_29_7") (pintype "power_in"))
      (node (ref "U2") (pin "29_8") (pinfunction "GND_29_8") (pintype "power_in"))
      (node (ref "U2") (pin "29_9") (pinfunction "GND_29_9") (pintype "power_in"))
      (node (ref "U3") (pin "13") (pinfunction "GND_13") (pintype "power_in"))
      (node (ref "U4") (pin "1") (pinfunction "CTG_1") (pintype "power_in"))
      (node (ref "U4") (pin "4") (pinfunction "GND_4") (pintype "power_in"))
      (node (ref "U4") (pin "6") (pinfunction "QSTRT_6") (pintype "input"))
      (node (ref "U4") (pin "9") (pinfunction "EP_9") (pintype "power_in"))
    )
    (net (code "14") (name "GPIO8") (class "Default")
      (node (ref "R1") (pin "1") (pinfunction "1_1") (pintype "passive"))
      (node (ref "U2") (pin "10") (pinfunction "IO8_10") (pintype "bidirectional"))
    )
    (net (code "15") (name "I2C_PW") (class "Default")
      (node (ref "C1") (pin "1") (pinfunction "1_1") (pintype "passive"))
      (node (ref "C2") (pin "1") (pinfunction "1_1") (pintype "passive"))
      (node (ref "R1_PINH") (pin "2") (pinfunction "2_2") (pintype "passive"))
      (node (ref "R2_PINH") (pin "2") (pinfunction "2_2") (pintype "passive"))
      (node (ref "SENSOR2") (pin "2") (pinfunction "CSB_2") (pintype "input"))
      (node (ref "SENSOR2") (pin "6") (pinfunction "VDDIO_6") (pintype "power_in"))
      (node (ref "SENSOR2") (pin "8") (pinfunction "VDD_8") (pintype "power_in"))
      (node (ref "U2") (pin "17") (pinfunction "IO19_17") (pintype "bidirectional"))
    )
    (net (code "16") (name "INT_RTC") (class "Default")
      (node (ref "INT_RTC") (pin "TP") (pinfunction "TP_TP") (pintype "input"))
      (node (ref "R1_PINH1") (pin "1") (pinfunction "1_1") (pintype "passive"))
      (node (ref "U2") (pin "8") (pinfunction "IO0_8") (pintype "bidirectional"))
      (node (ref "U3") (pin "3") (pinfunction "SQW/~{INT}_3") (pintype "output"))
    )
    (net (code "17") (name "IO{slash}BOOT") (class "Default")
      (node (ref "BOOT_BUTTON") (pin "3") (pinfunction "3_3") (pintype "passive"))
      (node (ref "BOOT_BUTTON") (pin "4") (pinfunction "4_4") (pintype "passive"))
      (node (ref "C6") (pin "1") (pinfunction "1_1") (pintype "passive"))
      (node (ref "R_BOOT") (pin "1") (pinfunction "1_1") (pintype "passive"))
      (node (ref "U2") (pin "15") (pinfunction "IO9_15") (pintype "bidirectional"))
    )
    (net (code "18") (name "IO{slash}CHANGE") (class "Default")
      (node (ref "C10") (pin "1") (pinfunction "1_1") (pintype "passive"))
      (node (ref "CHANGE_BUTTON") (pin "3") (pinfunction "3_3") (pintype "passive"))
      (node (ref "CHANGE_BUTTON") (pin "4") (pinfunction "4_4") (pintype "passive"))
      (node (ref "R_CHANGE") (pin "1") (pinfunction "1_1") (pintype "passive"))
      (node (ref "U2") (pin "23") (pinfunction "IO15_23") (pintype "bidirectional"))
    )
    (net (code "19") (name "MISO") (class "Default")
      (node (ref "D12") (pin "2") (pinfunction "2_2") (pintype "passive"))
      (node (ref "J4") (pin "P7") (pinfunction "DAT0_P7") (pintype "bidirectional"))
      (node (ref "MISO") (pin "TP") (pinfunction "TP_TP") (pintype "input"))
      (node (ref "R8") (pin "2") (pinfunction "2_2") (pintype "passive"))
      (node (ref "U1") (pin "2") (pinfunction "DO(IO1)_2") (pintype "bidirectional"))
      (node (ref "U2") (pin "27") (pinfunction "IO2_27") (pintype "bidirectional"))
    )
    (net (code "20") (name "MOSI") (class "Default")
      (node (ref "D11") (pin "2") (pinfunction "2_2") (pintype "passive"))
      (node (ref "J1") (pin "14") (pinfunction "14_14") (pintype "bidirectional"))
      (node (ref "J4") (pin "P3") (pinfunction "CMD_P3") (pintype "bidirectional"))
      (node (ref "MOSI") (pin "TP") (pinfunction "TP_TP") (pintype "input"))
      (node (ref "R7") (pin "2") (pinfunction "2_2") (pintype "passive"))
      (node (ref "U1") (pin "5") (pinfunction "DI(IO0)_5") (pintype "bidirectional"))
      (node (ref "U2") (pin "7") (pinfunction "IO7_7") (pintype "bidirectional"))
    )
    (net (code "21") (name "Net-(CHG_LED-PadC)") (class "Default")
      (node (ref "CHG_LED") (pin "C") (pinfunction "C_C") (pintype "passive"))
      (node (ref "R1_BAT") (pin "1") (pinfunction "1_1") (pintype "passive"))
    )
    (net (code "22") (name "Net-(D2-CATHODE)") (class "Default")
      (node (ref "C1_BAT1") (pin "1") (pinfunction "1_1") (pintype "passive"))
      (node (ref "D2") (pin "1") (pinfunction "CATHODE_1") (pintype "bidirectional"))
      (node (ref "IC4") (pin "1") (pinfunction "VIN_1") (pintype "bidirectional"))
      (node (ref "IC4") (pin "3") (pinfunction "CE_3") (pintype "bidirectional"))
    )
    (net (code "23") (name "Net-(D3-A)") (class "Default")
      (node (ref "C4") (pin "1") (pinfunction "1_1") (pintype "passive"))
      (node (ref "D3") (pin "2") (pinfunction "A_2") (pintype "bidirectional"))
      (node (ref "D4") (pin "1") (pinfunction "K_1") (pintype "bidirectional"))
    )
    (net (code "24") (name "Net-(D7-CATHODE)") (class "Default")
      (node (ref "D7") (pin "1") (pinfunction "CATHODE_1") (pintype "bidirectional"))
      (node (ref "R_CAPACITOR") (pin "1") (pinfunction "1_1") (pintype "passive"))
    )
    (net (code "25") (name "Net-(EPD_C1-Pad1)") (class "Default")
      (node (ref "EPD_C1") (pin "1") (pinfunction "1_1") (pintype "passive"))
      (node (ref "J1") (pin "4") (pinfunction "4_4") (pintype "bidirectional"))
    )
    (net (code "26") (name "Net-(EPD_C2-Pad1)") (class "Default")
      (node (ref "EPD_C2") (pin "1") (pinfunction "1_1") (pintype "passive"))
      (node (ref "J1") (pin "5") (pinfunction "5_5") (pintype "bidirectional"))
    )
    (net (code "27") (name "Net-(EPD_C6-Pad1)") (class "Default")
      (node (ref "EPD_C6") (pin "1") (pinfunction "1_1") (pintype "passive"))
      (node (ref "J1") (pin "18") (pinfunction "18_18") (pintype "bidirectional"))
    )
    (net (code "28") (name "Net-(EPD_C7-Pad1)") (class "Default")
      (node (ref "EPD_C7") (pin "1") (pinfunction "1_1") (pintype "passive"))
      (node (ref "J1") (pin "19") (pinfunction "19_19") (pintype "bidirectional"))
    )
    (net (code "29") (name "Net-(EPD_C8-Pad1)") (class "Default")
      (node (ref "EPD_C8") (pin "1") (pinfunction "1_1") (pintype "passive"))
      (node (ref "J1") (pin "20") (pinfunction "20_20") (pintype "bidirectional"))
    )
    (net (code "30") (name "Net-(EPD_C10-Pad1)") (class "Default")
      (node (ref "EPD_C10") (pin "1") (pinfunction "1_1") (pintype "passive"))
      (node (ref "J1") (pin "22") (pinfunction "22_22") (pintype "bidirectional"))
    )
    (net (code "31") (name "Net-(EPD_C12-Pad1)") (class "Default")
      (node (ref "EPD_C12") (pin "1") (pinfunction "1_1") (pintype "passive"))
      (node (ref "J1") (pin "24") (pinfunction "24_24") (pintype "bidirectional"))
    )
    (net (code "32") (name "Net-(IC1-CT)") (class "Default")
      (node (ref "C_DELAY") (pin "1") (pinfunction "1_1") (pintype "passive"))
      (node (ref "IC1") (pin "5") (pinfunction "CT_5") (pintype "bidirectional"))
    )
    (net (code "33") (name "Net-(J2-PadA5)") (class "Default")
      (node (ref "J2") (pin "A5") (pinfunction "A5_A5") (pintype "bidirectional"))
      (node (ref "R2-USB1") (pin "2") (pinfunction "2_2") (pintype "passive"))
    )
    (net (code "34") (name "Net-(J2-PadB5)") (class "Default")
      (node (ref "J2") (pin "B5") (pinfunction "B5_B5") (pintype "bidirectional"))
      (node (ref "R2-USB") (pin "1") (pinfunction "1_1") (pintype "passive"))
    )
    (net (code "35") (name "Net-(MCP73831-PROG)") (class "Default")
      (node (ref "MCP73831") (pin "5") (pinfunction "PROG_5") (pintype "input"))
      (node (ref "R2_BAT") (pin "2") (pinfunction "2_2") (pintype "passive"))
    )
    (net (code "36") (name "Net-(MCP73831-STAT)") (class "Default")
      (node (ref "MCP73831") (pin "1") (pinfunction "STAT_1") (pintype "output"))
      (node (ref "R1_BAT") (pin "2") (pinfunction "2_2") (pintype "passive"))
    )
    (net (code "37") (name "PREVGH") (class "Default")
      (node (ref "D5") (pin "1") (pinfunction "K_1") (pintype "bidirectional"))
      (node (ref "EPD_C9") (pin "1") (pinfunction "1_1") (pintype "passive"))
      (node (ref "J1") (pin "21") (pinfunction "21_21") (pintype "bidirectional"))
    )
    (net (code "38") (name "PREVGL") (class "Default")
      (node (ref "D4") (pin "2") (pinfunction "A_2") (pintype "bidirectional"))
      (node (ref "EPD_C11") (pin "1") (pinfunction "1_1") (pintype "passive"))
      (node (ref "J1") (pin "23") (pinfunction "23_23") (pintype "bidirectional"))
    )
    (net (code "39") (name "RESE") (class "Default")
      (node (ref "J1") (pin "3") (pinfunction "3_3") (pintype "bidirectional"))
      (node (ref "Q3") (pin "2") (pinfunction "S_2") (pintype "bidirectional"))
      (node (ref "R3") (pin "2") (pinfunction "2_2") (pintype "passive"))
    )
    (net (code "40") (name "RESE'") (class "Default")
      (node (ref "R2") (pin "2") (pinfunction "2_2") (pintype "passive"))
      (node (ref "R3") (pin "1") (pinfunction "1_1") (pintype "passive"))
      (node (ref "SJ1") (pin "2") (pinfunction "2_2") (pintype "passive"))
    )
    (net (code "41") (name "RESET") (class "Default")
      (node (ref "C5") (pin "1") (pinfunction "1_1") (pintype "passive"))
      (node (ref "IC1") (pin "1") (pinfunction "VOUT_1") (pintype "bidirectional"))
      (node (ref "RESET_BUTTON") (pin "3") (pinfunction "3_3") (pintype "passive"))
      (node (ref "RESET_BUTTON") (pin "4") (pinfunction "4_4") (pintype "passive"))
      (node (ref "R_RESET") (pin "1") (pinfunction "1_1") (pintype "passive"))
      (node (ref "U2") (pin "3") (pinfunction "EN_3") (pintype "input"))
    )
    (net (code "42") (name "RTC_RST") (class "Default")
      (node (ref "U2") (pin "16") (pinfunction "IO18_16") (pintype "bidirectional"))
      (node (ref "U3") (pin "4") (pinfunction "~{RST}_4") (pintype "input"))
    )
    (net (code "43") (name "RX") (class "Default")
      (node (ref "RX") (pin "TP") (pinfunction "TP_TP") (pintype "input"))
      (node (ref "U2") (pin "24") (pinfunction "RXD0/GPIO17_24") (pintype "bidirectional"))
    )
    (net (code "44") (name "SCK") (class "Default")
      (node (ref "D10") (pin "2") (pinfunction "2_2") (pintype "passive"))
      (node (ref "J1") (pin "13") (pinfunction "13_13") (pintype "bidirectional"))
      (node (ref "J4") (pin "P5") (pinfunction "CLK_P5") (pintype "bidirectional"))
      (node (ref "R6") (pin "2") (pinfunction "2_2") (pintype "passive"))
      (node (ref "SCK") (pin "TP") (pinfunction "TP_TP") (pintype "input"))
      (node (ref "U1") (pin "6") (pinfunction "CLK_6") (pintype "input"))
      (node (ref "U2") (pin "6") (pinfunction "IO6_6") (pintype "bidirectional"))
    )
    (net (code "45") (name "SCL") (class "Default")
      (node (ref "J3") (pin "4") (pinfunction "4_4") (pintype "passive"))
      (node (ref "R2_PINH") (pin "1") (pinfunction "1_1") (pintype "passive"))
      (node (ref "SENSOR2") (pin "4") (pinfunction "SCK_4") (pintype "input"))
      (node (ref "U2") (pin "20") (pinfunction "IO22_20") (pintype "bidirectional"))
      (node (ref "U3") (pin "16") (pinfunction "SCL_16") (pintype "input"))
      (node (ref "U4") (pin "7") (pinfunction "SCL_7") (pintype "input"))
    )
    (net (code "46") (name "SDA") (class "Default")
      (node (ref "J3") (pin "3") (pinfunction "3_3") (pintype "passive"))
      (node (ref "R1_PINH") (pin "1") (pinfunction "1_1") (pintype "passive"))
      (node (ref "SENSOR2") (pin "3") (pinfunction "SDI_3") (pintype "bidirectional"))
      (node (ref "U2") (pin "19") (pinfunction "IO21_19") (pintype "bidirectional"))
      (node (ref "U3") (pin "15") (pinfunction "SDA_15") (pintype "bidirectional"))
      (node (ref "U4") (pin "8") (pinfunction "SDA_8") (pintype "bidirectional"))
    )
    (net (code "47") (name "SRC") (class "Default")
      (node (ref "C4") (pin "2") (pinfunction "2_2") (pintype "passive"))
      (node (ref "D5") (pin "2") (pinfunction "A_2") (pintype "bidirectional"))
      (node (ref "L1") (pin "1") (pinfunction "1_1") (pintype "passive"))
      (node (ref "Q3") (pin "3") (pinfunction "D_3") (pintype "bidirectional"))
    )
    (net (code "48") (name "SS_SD") (class "Default")
      (node (ref "D8") (pin "2") (pinfunction "2_2") (pintype "passive"))
      (node (ref "J4") (pin "P2") (pinfunction "CD/DAT3_P2") (pintype "bidirectional"))
      (node (ref "R10") (pin "2") (pinfunction "2_2") (pintype "passive"))
      (node (ref "U2") (pin "4") (pinfunction "IO4_4") (pintype "bidirectional"))
    )
    (net (code "49") (name "TX") (class "Default")
      (node (ref "TX") (pin "TP") (pinfunction "TP_TP") (pintype "input"))
      (node (ref "U2") (pin "25") (pinfunction "TXD0/GPIO16_25") (pintype "bidirectional"))
    )
    (net (code "50") (name "USB_D+") (class "Default")
      (node (ref "D1") (pin "1") (pinfunction "I/O1_1_1") (pintype "bidirectional"))
      (node (ref "U2") (pin "14") (pinfunction "IO13_14") (pintype "bidirectional"))
    )
    (net (code "51") (name "USB_D-") (class "Default")
      (node (ref "D1") (pin "3") (pinfunction "I/O2_1_3") (pintype "bidirectional"))
      (node (ref "U2") (pin "13") (pinfunction "IO12_13") (pintype "bidirectional"))
    )
    (net (code "52") (name "VBAT") (class "Default")
      (node (ref "C2_BAT") (pin "1") (pinfunction "1_1") (pintype "passive"))
      (node (ref "MCP73831") (pin "3") (pinfunction "VBAT_3") (pintype "power_in"))
      (node (ref "Q1") (pin "3") (pinfunction "D_3") (pintype "bidirectional"))
      (node (ref "U4") (pin "2") (pinfunction "CELL_2") (pintype "power_in"))
      (node (ref "U4") (pin "3") (pinfunction "VDD_3") (pintype "power_in"))
      (node (ref "VBAT") (pin "TP") (pinfunction "TP_TP") (pintype "input"))
    )
    (net (code "53") (name "VBUS") (class "Default")
      (node (ref "C1_BAT") (pin "1") (pinfunction "1_1") (pintype "passive"))
      (node (ref "C4_USB") (pin "1") (pinfunction "1_1") (pintype "passive"))
      (node (ref "C5_USB") (pin "1") (pinfunction "1_1") (pintype "passive"))
      (node (ref "CHG_LED") (pin "A") (pinfunction "A_A") (pintype "passive"))
      (node (ref "D1") (pin "5") (pinfunction "VBUS_5") (pintype "bidirectional"))
      (node (ref "D2") (pin "2") (pinfunction "ANODE_2") (pintype "bidirectional"))
      (node (ref "MCP73831") (pin "4") (pinfunction "VIN_4") (pintype "power_in"))
      (node (ref "PFMF.050.1") (pin "1") (pinfunction "1_1") (pintype "passive"))
      (node (ref "Q1") (pin "1") (pinfunction "G_1") (pintype "bidirectional"))
      (node (ref "R1_PWRUSB") (pin "2") (pinfunction "2_2") (pintype "passive"))
      (node (ref "VBUS") (pin "TP") (pinfunction "TP_TP") (pintype "input"))
    )
    (net (code "54") (name "VRTC") (class "Default")
      (node (ref "C10_SUPERCAP") (pin "2") (pinfunction "2_2") (pintype "passive"))
      (node (ref "C8") (pin "1") (pinfunction "1_1") (pintype "passive"))
      (node (ref "R_CAPACITOR") (pin "2") (pinfunction "2_2") (pintype "passive"))
      (node (ref "U3") (pin "14") (pinfunction "VBAT_14") (pintype "power_in"))
    )
    (net (code "55") (name "VUSB") (class "Default")
      (node (ref "J2") (pin "A4") (pinfunction "A4_A4") (pintype "bidirectional"))
      (node (ref "J2") (pin "A9") (pinfunction "A9_A9") (pintype "bidirectional"))
      (node (ref "J2") (pin "B4") (pinfunction "B4_B4") (pintype "bidirectional"))
      (node (ref "J2") (pin "B9") (pinfunction "B9_B9") (pintype "bidirectional"))
      (node (ref "PFMF.050.1") (pin "2") (pinfunction "2_2") (pintype "passive"))
    )
    (net (code "56") (name "unconnected-(IC1-NC-Pad4)") (class "Default")
      (node (ref "IC1") (pin "4") (pinfunction "NC_4") (pintype "no_connect"))
    )
    (net (code "57") (name "unconnected-(IC4-NC-Pad4)") (class "Default")
      (node (ref "IC4") (pin "4") (pinfunction "NC_4") (pintype "no_connect"))
    )
    (net (code "58") (name "unconnected-(J1-Pad1)") (class "Default")
      (node (ref "J1") (pin "1") (pinfunction "1_1") (pintype "bidirectional"))
    )
    (net (code "59") (name "unconnected-(J1-Pad6)") (class "Default")
      (node (ref "J1") (pin "6") (pinfunction "6_6") (pintype "bidirectional"))
    )
    (net (code "60") (name "unconnected-(J1-Pad7)") (class "Default")
      (node (ref "J1") (pin "7") (pinfunction "7_7") (pintype "bidirectional"))
    )
    (net (code "61") (name "unconnected-(J2-PadA8)") (class "Default")
      (node (ref "J2") (pin "A8") (pinfunction "A8_A8") (pintype "bidirectional"))
    )
    (net (code "62") (name "unconnected-(J2-PadB8)") (class "Default")
      (node (ref "J2") (pin "B8") (pinfunction "B8_B8") (pintype "bidirectional"))
    )
    (net (code "63") (name "unconnected-(J4-DAT1-PadP8)") (class "Default")
      (node (ref "J4") (pin "P8") (pinfunction "DAT1_P8") (pintype "bidirectional"))
    )
    (net (code "64") (name "unconnected-(J4-DAT2-PadP1)") (class "Default")
      (node (ref "J4") (pin "P1") (pinfunction "DAT2_P1") (pintype "bidirectional"))
    )
    (net (code "65") (name "unconnected-(J4-DETECTION_1-PadS1)") (class "Default")
      (node (ref "J4") (pin "S1") (pinfunction "DETECTION_1_S1") (pintype "bidirectional"))
    )
    (net (code "66") (name "unconnected-(J4-DETECTION_2-PadS2)") (class "Default")
      (node (ref "J4") (pin "S2") (pinfunction "DETECTION_2_S2") (pintype "bidirectional"))
    )
    (net (code "67") (name "unconnected-(J4-GND_4-PadG4)") (class "Default")
      (node (ref "J4") (pin "G4") (pinfunction "GND_4_G4") (pintype "bidirectional"))
    )
    (net (code "68") (name "unconnected-(Q1-S-Pad2)") (class "Default")
      (node (ref "Q1") (pin "2") (pinfunction "S_2") (pintype "bidirectional"))
    )
    (net (code "69") (name "unconnected-(U1-EXP-Pad9)") (class "Default")
      (node (ref "U1") (pin "9") (pinfunction "EXP_9") (pintype "passive"))
    )
    (net (code "70") (name "unconnected-(U2-NC-Pad22)") (class "Default")
      (node (ref "U2") (pin "22") (pinfunction "NC_22") (pintype "no_connect"))
    )
    (net (code "71") (name "unconnected-(U4-~{ALERT}-Pad5)") (class "Default")
      (node (ref "U4") (pin "5") (pinfunction "~{ALERT}_5") (pintype "output"))
    )
  )
)
